# EPD_DRIVER.net
KiCad netlist of a schematic drawn in EAGLE
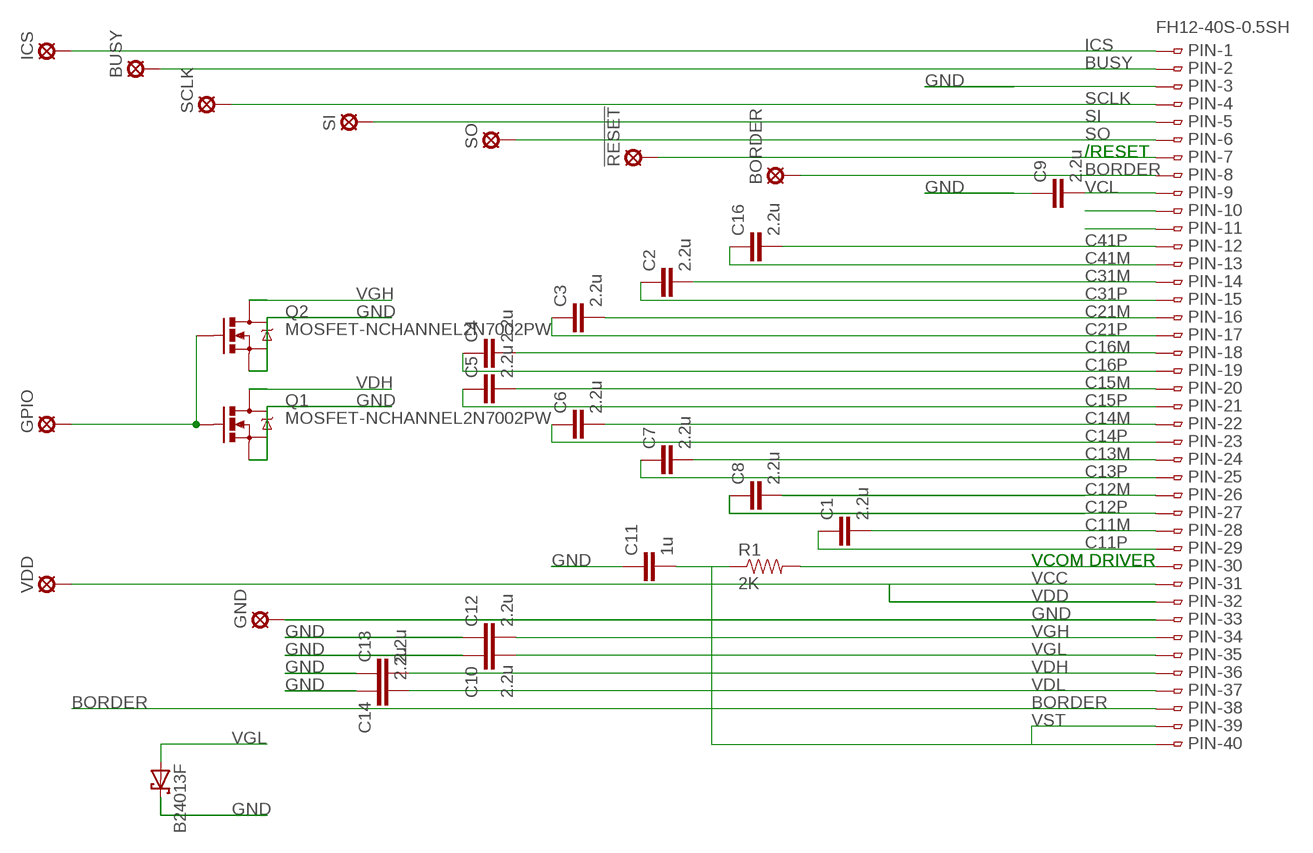
[diagram p0: schematic, sheet 1]

(export (version "E")
  (design (tool "Eeschema 10.0.6"))
  (components
    (comp (ref "!RESET")
      (value "SE11")
      (footprint "eagle-import:SE11")
      (libsource (lib "eagle-import") (part "SE11"))
    )
    (comp (ref "B24013F")
      (value "SCHOTTKY-DIODESMD")
      (footprint "eagle-import:SMB")
      (libsource (lib "eagle-import") (part "SCHOTTKY-DIODESMD"))
    )
    (comp (ref "BORDER")
      (value "SE11")
      (footprint "eagle-import:SE11")
      (libsource (lib "eagle-import") (part "SE11"))
    )
    (comp (ref "BUSY")
      (value "SE11")
      (footprint "eagle-import:SE11")
      (libsource (lib "eagle-import") (part "SE11"))
    )
    (comp (ref "C1")
      (value "2.2u")
      (footprint "eagle-import:0603-CAP")
      (libsource (lib "eagle-import") (part "CAP0603-CAP"))
    )
    (comp (ref "C2")
      (value "2.2u")
      (footprint "eagle-import:0603-CAP")
      (libsource (lib "eagle-import") (part "CAP0603-CAP"))
    )
    (comp (ref "C3")
      (value "2.2u")
      (footprint "eagle-import:0603-CAP")
      (libsource (lib "eagle-import") (part "CAP0603-CAP"))
    )
    (comp (ref "C4")
      (value "2.2u")
      (footprint "eagle-import:0603-CAP")
      (libsource (lib "eagle-import") (part "CAP0603-CAP"))
    )
    (comp (ref "C5")
      (value "2.2u")
      (footprint "eagle-import:0603-CAP")
      (libsource (lib "eagle-import") (part "CAP0603-CAP"))
    )
    (comp (ref "C6")
      (value "2.2u")
      (footprint "eagle-import:0603-CAP")
      (libsource (lib "eagle-import") (part "CAP0603-CAP"))
    )
    (comp (ref "C7")
      (value "2.2u")
      (footprint "eagle-import:0603-CAP")
      (libsource (lib "eagle-import") (part "CAP0603-CAP"))
    )
    (comp (ref "C8")
      (value "2.2u")
      (footprint "eagle-import:0603-CAP")
      (libsource (lib "eagle-import") (part "CAP0603-CAP"))
    )
    (comp (ref "C9")
      (value "2.2u")
      (footprint "eagle-import:0603-CAP")
      (libsource (lib "eagle-import") (part "CAP0603-CAP"))
    )
    (comp (ref "C10")
      (value "2.2u")
      (footprint "eagle-import:0603-CAP")
      (libsource (lib "eagle-import") (part "CAP0603-CAP"))
    )
    (comp (ref "C11")
      (value "1u")
      (footprint "eagle-import:0603-CAP")
      (libsource (lib "eagle-import") (part "CAP0603-CAP"))
    )
    (comp (ref "C12")
      (value "2.2u")
      (footprint "eagle-import:0603-CAP")
      (libsource (lib "eagle-import") (part "CAP0603-CAP"))
    )
    (comp (ref "C13")
      (value "2.2u")
      (footprint "eagle-import:0603-CAP")
      (libsource (lib "eagle-import") (part "CAP0603-CAP"))
    )
    (comp (ref "C14")
      (value "2.2u")
      (footprint "eagle-import:0603-CAP")
      (libsource (lib "eagle-import") (part "CAP0603-CAP"))
    )
    (comp (ref "C16")
      (value "2.2u")
      (footprint "eagle-import:0603-CAP")
      (libsource (lib "eagle-import") (part "CAP0603-CAP"))
    )
    (comp (ref "GND")
      (value "SE11")
      (footprint "eagle-import:SE11")
      (libsource (lib "eagle-import") (part "SE11"))
    )
    (comp (ref "GPIO")
      (value "SE11")
      (footprint "eagle-import:SE11")
      (libsource (lib "eagle-import") (part "SE11"))
    )
    (comp (ref "ICS")
      (value "SE11")
      (footprint "eagle-import:SE11")
      (libsource (lib "eagle-import") (part "SE11"))
    )
    (comp (ref "PIN")
      (value "FH12-40S-0.5SH")
      (footprint "eagle-import:FH12-40S-0.5SH")
      (fields (field (name "MPN") "FH12-40S-0.5SH(55)"))
      (libsource (lib "eagle-import") (part "FH12-40S-0.5SH"))
    )
    (comp (ref "Q1")
      (value "MOSFET-NCHANNEL2N7002PW")
      (footprint "eagle-import:SOT323")
      (libsource (lib "eagle-import") (part "MOSFET-NCHANNEL2N7002PW"))
    )
    (comp (ref "Q2")
      (value "MOSFET-NCHANNEL2N7002PW")
      (footprint "eagle-import:SOT323")
      (libsource (lib "eagle-import") (part "MOSFET-NCHANNEL2N7002PW"))
    )
    (comp (ref "R1")
      (value "2K")
      (footprint "eagle-import:0603-RES")
      (libsource (lib "eagle-import") (part "RESISTOR0603-RES"))
    )
    (comp (ref "SCLK")
      (value "SE11")
      (footprint "eagle-import:SE11")
      (libsource (lib "eagle-import") (part "SE11"))
    )
    (comp (ref "SI")
      (value "SE11")
      (footprint "eagle-import:SE11")
      (libsource (lib "eagle-import") (part "SE11"))
    )
    (comp (ref "SO")
      (value "SE11")
      (footprint "eagle-import:SE11")
      (libsource (lib "eagle-import") (part "SE11"))
    )
    (comp (ref "VDD")
      (value "SE11")
      (footprint "eagle-import:SE11")
      (libsource (lib "eagle-import") (part "SE11"))
    )
  )
  (nets
    (net (code "1") (name "/BORDER") (class "Default")
      (node (ref "BORDER") (pin "MP") (pinfunction "MP_MP") (pintype "passive"))
      (node (ref "PIN") (pin "38") (pinfunction "1_38") (pintype "passive"))
      (node (ref "PIN") (pin "8") (pinfunction "1_8") (pintype "passive"))
    )
    (net (code "2") (name "/GND") (class "Default")
      (node (ref "B24013F") (pin "C") (pinfunction "C_C") (pintype "passive"))
      (node (ref "C10") (pin "1") (pinfunction "1_1") (pintype "passive"))
      (node (ref "C11") (pin "1") (pinfunction "1_1") (pintype "passive"))
      (node (ref "C12") (pin "1") (pinfunction "1_1") (pintype "passive"))
      (node (ref "C13") (pin "1") (pinfunction "1_1") (pintype "passive"))
      (node (ref "C14") (pin "1") (pinfunction "1_1") (pintype "passive"))
      (node (ref "C9") (pin "1") (pinfunction "1_1") (pintype "passive"))
      (node (ref "PIN") (pin "3") (pinfunction "1_3") (pintype "passive"))
      (node (ref "Q1") (pin "2") (pinfunction "S_2") (pintype "passive"))
      (node (ref "Q2") (pin "2") (pinfunction "S_2") (pintype "passive"))
    )
    (net (code "3") (name "/VDH") (class "Default")
      (node (ref "C13") (pin "2") (pinfunction "2_2") (pintype "passive"))
      (node (ref "PIN") (pin "36") (pinfunction "1_36") (pintype "passive"))
      (node (ref "Q1") (pin "3") (pinfunction "D_3") (pintype "passive"))
    )
    (net (code "4") (name "/VGH") (class "Default")
      (node (ref "C10") (pin "2") (pinfunction "2_2") (pintype "passive"))
      (node (ref "PIN") (pin "34") (pinfunction "1_34") (pintype "passive"))
      (node (ref "Q2") (pin "3") (pinfunction "D_3") (pintype "passive"))
    )
    (net (code "5") (name "/VGL") (class "Default")
      (node (ref "B24013F") (pin "A") (pinfunction "A_A") (pintype "passive"))
      (node (ref "C12") (pin "2") (pinfunction "2_2") (pintype "passive"))
      (node (ref "PIN") (pin "35") (pinfunction "1_35") (pintype "passive"))
    )
    (net (code "6") (name "Net-(ICS-PadMP)") (class "Default")
      (node (ref "ICS") (pin "MP") (pinfunction "MP_MP") (pintype "passive"))
      (node (ref "PIN") (pin "1") (pinfunction "1_1") (pintype "passive"))
    )
    (net (code "7") (name "Net-(PINAA-1)") (class "Default")
      (node (ref "GND") (pin "MP") (pinfunction "MP_MP") (pintype "passive"))
      (node (ref "PIN") (pin "33") (pinfunction "1_33") (pintype "passive"))
    )
    (net (code "8") (name "Net-(PINAE-1)") (class "Default")
      (node (ref "C14") (pin "2") (pinfunction "2_2") (pintype "passive"))
      (node (ref "PIN") (pin "37") (pinfunction "1_37") (pintype "passive"))
    )
    (net (code "9") (name "Net-(PINAG-1)") (class "Default")
      (node (ref "C11") (pin "2") (pinfunction "2_2") (pintype "passive"))
      (node (ref "PIN") (pin "39") (pinfunction "1_39") (pintype "passive"))
      (node (ref "PIN") (pin "40") (pinfunction "1_40") (pintype "passive"))
      (node (ref "R1") (pin "1") (pinfunction "1_1") (pintype "passive"))
    )
    (net (code "10") (name "Net-(PINAH-1)") (class "Default")
      (node (ref "PIN") (pin "4") (pinfunction "1_4") (pintype "passive"))
      (node (ref "SCLK") (pin "MP") (pinfunction "MP_MP") (pintype "passive"))
    )
    (net (code "11") (name "Net-(PINAJ-1)") (class "Default")
      (node (ref "PIN") (pin "5") (pinfunction "1_5") (pintype "passive"))
      (node (ref "SI") (pin "MP") (pinfunction "MP_MP") (pintype "passive"))
    )
    (net (code "12") (name "Net-(PINAK-1)") (class "Default")
      (node (ref "PIN") (pin "6") (pinfunction "1_6") (pintype "passive"))
      (node (ref "SO") (pin "MP") (pinfunction "MP_MP") (pintype "passive"))
    )
    (net (code "13") (name "Net-(PINAL-1)") (class "Default")
      (node (ref "!RESET") (pin "MP") (pinfunction "MP_MP") (pintype "passive"))
      (node (ref "PIN") (pin "7") (pinfunction "1_7") (pintype "passive"))
    )
    (net (code "14") (name "Net-(PINAN-1)") (class "Default")
      (node (ref "C9") (pin "2") (pinfunction "2_2") (pintype "passive"))
      (node (ref "PIN") (pin "9") (pinfunction "1_9") (pintype "passive"))
    )
    (net (code "15") (name "Net-(PIND-1)") (class "Default")
      (node (ref "C16") (pin "2") (pinfunction "2_2") (pintype "passive"))
      (node (ref "PIN") (pin "12") (pinfunction "1_12") (pintype "passive"))
    )
    (net (code "16") (name "Net-(PINE-1)") (class "Default")
      (node (ref "C16") (pin "1") (pinfunction "1_1") (pintype "passive"))
      (node (ref "PIN") (pin "13") (pinfunction "1_13") (pintype "passive"))
    )
    (net (code "17") (name "Net-(PINF-1)") (class "Default")
      (node (ref "C2") (pin "2") (pinfunction "2_2") (pintype "passive"))
      (node (ref "PIN") (pin "14") (pinfunction "1_14") (pintype "passive"))
    )
    (net (code "18") (name "Net-(PING-1)") (class "Default")
      (node (ref "C2") (pin "1") (pinfunction "1_1") (pintype "passive"))
      (node (ref "PIN") (pin "15") (pinfunction "1_15") (pintype "passive"))
    )
    (net (code "19") (name "Net-(PINH-1)") (class "Default")
      (node (ref "C3") (pin "2") (pinfunction "2_2") (pintype "passive"))
      (node (ref "PIN") (pin "16") (pinfunction "1_16") (pintype "passive"))
    )
    (net (code "20") (name "Net-(PINI-1)") (class "Default")
      (node (ref "C3") (pin "1") (pinfunction "1_1") (pintype "passive"))
      (node (ref "PIN") (pin "17") (pinfunction "1_17") (pintype "passive"))
    )
    (net (code "21") (name "Net-(PINJ-1)") (class "Default")
      (node (ref "C4") (pin "2") (pinfunction "2_2") (pintype "passive"))
      (node (ref "PIN") (pin "18") (pinfunction "1_18") (pintype "passive"))
    )
    (net (code "22") (name "Net-(PINK-1)") (class "Default")
      (node (ref "C4") (pin "1") (pinfunction "1_1") (pintype "passive"))
      (node (ref "PIN") (pin "19") (pinfunction "1_19") (pintype "passive"))
    )
    (net (code "23") (name "Net-(PINL-1)") (class "Default")
      (node (ref "BUSY") (pin "MP") (pinfunction "MP_MP") (pintype "passive"))
      (node (ref "PIN") (pin "2") (pinfunction "1_2") (pintype "passive"))
    )
    (net (code "24") (name "Net-(PINM-1)") (class "Default")
      (node (ref "C5") (pin "2") (pinfunction "2_2") (pintype "passive"))
      (node (ref "PIN") (pin "20") (pinfunction "1_20") (pintype "passive"))
    )
    (net (code "25") (name "Net-(PINN-1)") (class "Default")
      (node (ref "C5") (pin "1") (pinfunction "1_1") (pintype "passive"))
      (node (ref "PIN") (pin "21") (pinfunction "1_21") (pintype "passive"))
    )
    (net (code "26") (name "Net-(PINO-1)") (class "Default")
      (node (ref "C6") (pin "2") (pinfunction "2_2") (pintype "passive"))
      (node (ref "PIN") (pin "22") (pinfunction "1_22") (pintype "passive"))
    )
    (net (code "27") (name "Net-(PINP-1)") (class "Default")
      (node (ref "C6") (pin "1") (pinfunction "1_1") (pintype "passive"))
      (node (ref "PIN") (pin "23") (pinfunction "1_23") (pintype "passive"))
    )
    (net (code "28") (name "Net-(PINQ-1)") (class "Default")
      (node (ref "C7") (pin "2") (pinfunction "2_2") (pintype "passive"))
      (node (ref "PIN") (pin "24") (pinfunction "1_24") (pintype "passive"))
    )
    (net (code "29") (name "Net-(PINR-1)") (class "Default")
      (node (ref "C7") (pin "1") (pinfunction "1_1") (pintype "passive"))
      (node (ref "PIN") (pin "25") (pinfunction "1_25") (pintype "passive"))
    )
    (net (code "30") (name "Net-(PINS-1)") (class "Default")
      (node (ref "C8") (pin "2") (pinfunction "2_2") (pintype "passive"))
      (node (ref "PIN") (pin "26") (pinfunction "1_26") (pintype "passive"))
    )
    (net (code "31") (name "Net-(PINT-1)") (class "Default")
      (node (ref "C8") (pin "1") (pinfunction "1_1") (pintype "passive"))
      (node (ref "PIN") (pin "27") (pinfunction "1_27") (pintype "passive"))
    )
    (net (code "32") (name "Net-(PINU-1)") (class "Default")
      (node (ref "C1") (pin "2") (pinfunction "2_2") (pintype "passive"))
      (node (ref "PIN") (pin "28") (pinfunction "1_28") (pintype "passive"))
    )
    (net (code "33") (name "Net-(PINV-1)") (class "Default")
      (node (ref "C1") (pin "1") (pinfunction "1_1") (pintype "passive"))
      (node (ref "PIN") (pin "29") (pinfunction "1_29") (pintype "passive"))
    )
    (net (code "34") (name "Net-(PINX-1)") (class "Default")
      (node (ref "PIN") (pin "30") (pinfunction "1_30") (pintype "passive"))
      (node (ref "R1") (pin "2") (pinfunction "2_2") (pintype "passive"))
    )
    (net (code "35") (name "Net-(PINY-1)") (class "Default")
      (node (ref "PIN") (pin "31") (pinfunction "1_31") (pintype "passive"))
      (node (ref "PIN") (pin "32") (pinfunction "1_32") (pintype "passive"))
      (node (ref "VDD") (pin "MP") (pinfunction "MP_MP") (pintype "passive"))
    )
    (net (code "36") (name "Net-(Q1-G)") (class "Default")
      (node (ref "GPIO") (pin "MP") (pinfunction "MP_MP") (pintype "passive"))
      (node (ref "Q1") (pin "1") (pinfunction "G_1") (pintype "passive"))
      (node (ref "Q2") (pin "1") (pinfunction "G_1") (pintype "passive"))
    )
    (net (code "37") (name "unconnected-(PINB-1-Pad10)") (class "Default")
      (node (ref "PIN") (pin "10") (pinfunction "1_10") (pintype "passive"))
    )
    (net (code "38") (name "unconnected-(PINC-1-Pad11)") (class "Default")
      (node (ref "PIN") (pin "11") (pinfunction "1_11") (pintype "passive"))
    )
  )
)
